# v01.net
KiCad netlist of a schematic drawn in EAGLE
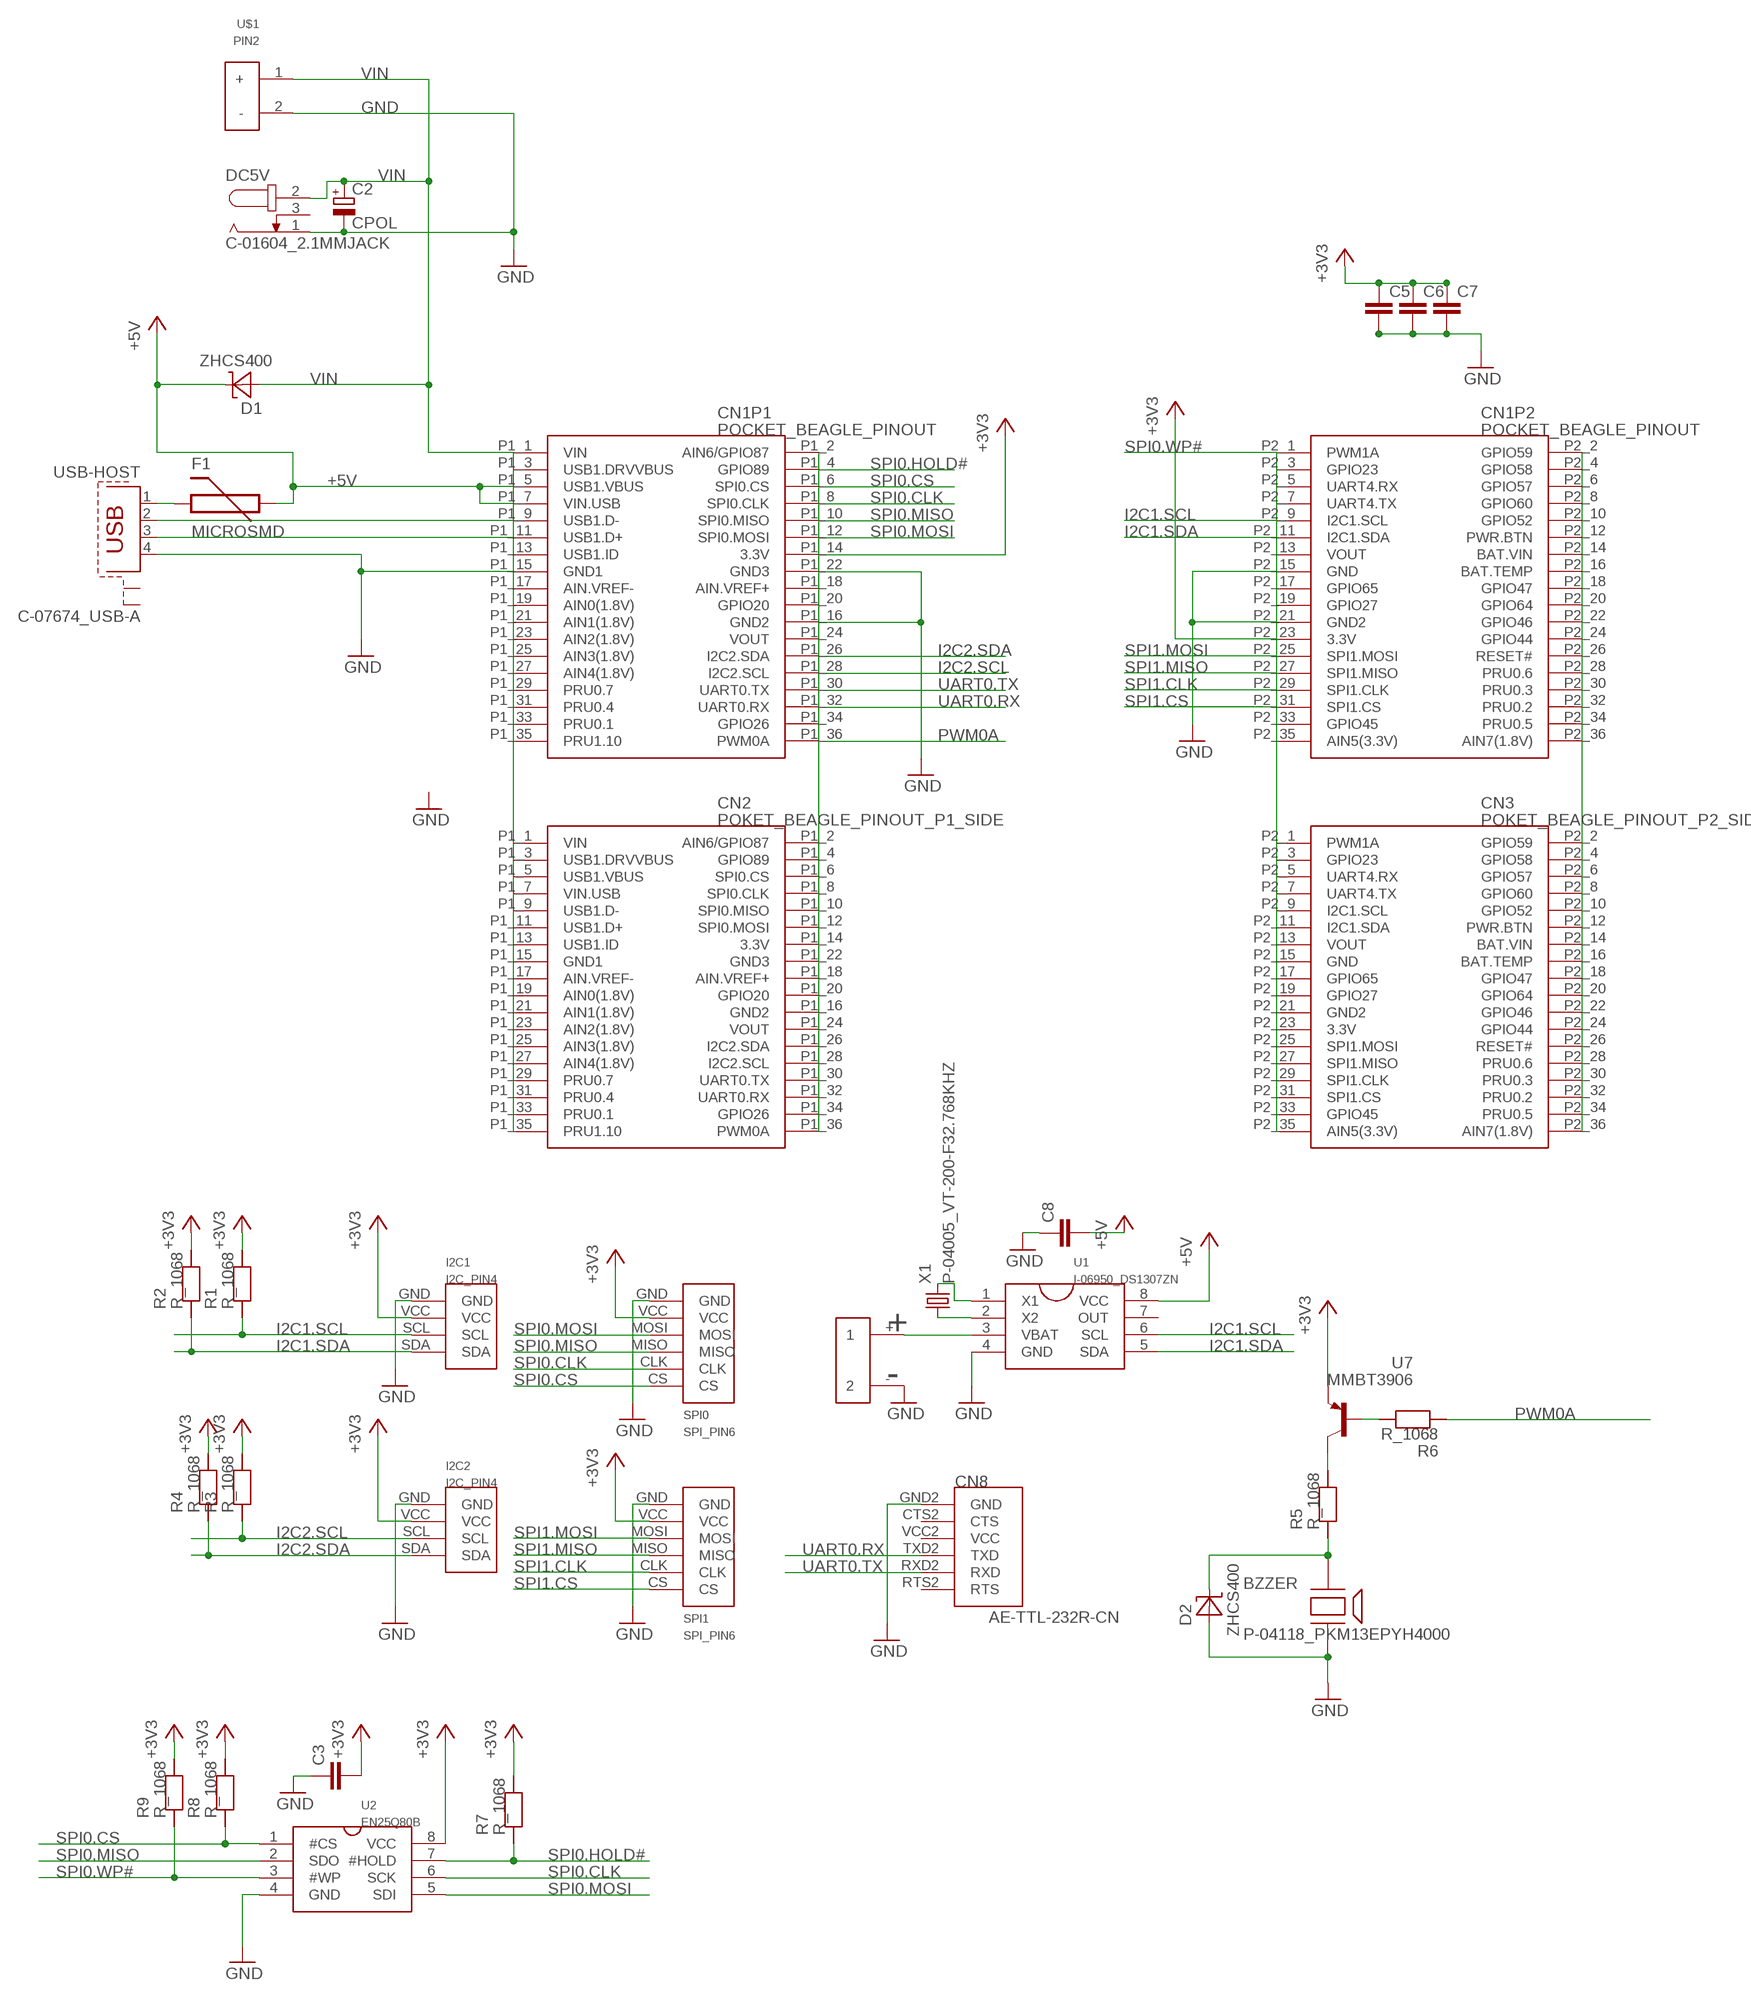
[diagram p0: schematic, sheet 1]

(export (version "E")
  (design (tool "Eeschema 10.0.6"))
  (components
    (comp (ref "BZZER")
      (value "P-04118_PKM13EPYH4000")
      (footprint "eagle-import:PKM13EPYH4000")
      (libsource (lib "eagle-import") (part "P-04118_PKM13EPYH4000"))
    )
    (comp (ref "C2")
      (value "CPOL")
      (footprint "eagle-import:153CLV-0605")
      (libsource (lib "eagle-import") (part "CPOL"))
    )
    (comp (ref "C3")
      (value "C_1068")
      (footprint "eagle-import:C0603")
      (libsource (lib "eagle-import") (part "C_1068"))
    )
    (comp (ref "C5")
      (value "C_2012")
      (footprint "eagle-import:C0805K")
      (libsource (lib "eagle-import") (part "C_2012"))
    )
    (comp (ref "C6")
      (value "C_1068")
      (footprint "eagle-import:C0603")
      (libsource (lib "eagle-import") (part "C_1068"))
    )
    (comp (ref "C7")
      (value "C_1068")
      (footprint "eagle-import:C0603")
      (libsource (lib "eagle-import") (part "C_1068"))
    )
    (comp (ref "C8")
      (value "C_1068")
      (footprint "eagle-import:C0603")
      (libsource (lib "eagle-import") (part "C_1068"))
    )
    (comp (ref "CN1")
      (value "POCKET_BEAGLE_PINOUT")
      (footprint "eagle-import:POCKET_BEAGLE_PINOUT")
      (libsource (lib "eagle-import") (part "POCKET_BEAGLE_PINOUT"))
    )
    (comp (ref "CN2")
      (value "POKET_BEAGLE_PINOUT_P1_SIDE")
      (footprint "eagle-import:POKET_BEAGLE_PINOUT_P1_SIDE")
      (libsource (lib "eagle-import") (part "POKET_BEAGLE_PINOUT_P1_SIDE"))
    )
    (comp (ref "CN3")
      (value "POKET_BEAGLE_PINOUT_P2_SIDE")
      (footprint "eagle-import:POKET_BEAGLE_PINOUT_P2_SIDE")
      (libsource (lib "eagle-import") (part "POKET_BEAGLE_PINOUT_P2_SIDE"))
    )
    (comp (ref "CN8")
      (value "AE-TTL-232R-CN")
      (footprint "eagle-import:AE-TTL-232R-CN")
      (libsource (lib "eagle-import") (part "AE-TTL-232R-CN"))
    )
    (comp (ref "CR2032")
      (value "P-00706_CH25-2032LF")
      (footprint "eagle-import:CH25-2032LF")
      (libsource (lib "eagle-import") (part "P-00706_CH25-2032LF"))
    )
    (comp (ref "D1")
      (value "ZHCS400")
      (footprint "eagle-import:SOD323-W")
      (libsource (lib "eagle-import") (part "ZHCS400"))
    )
    (comp (ref "D2")
      (value "ZHCS400")
      (footprint "eagle-import:SOD323-W")
      (libsource (lib "eagle-import") (part "ZHCS400"))
    )
    (comp (ref "DC5V")
      (value "C-01604_2.1MMJACK")
      (footprint "eagle-import:2.1MMJACK")
      (libsource (lib "eagle-import") (part "C-01604_2.1MMJACK"))
    )
    (comp (ref "F1")
      (value "MICROSMD")
      (footprint "eagle-import:MICROSMD")
      (libsource (lib "eagle-import") (part "MICROSMD"))
    )
    (comp (ref "I2C1")
      (value "I2C_PIN4")
      (footprint "eagle-import:I2C_PIN4")
      (libsource (lib "eagle-import") (part "I2C_PIN4"))
    )
    (comp (ref "I2C2")
      (value "I2C_PIN4")
      (footprint "eagle-import:I2C_PIN4")
      (libsource (lib "eagle-import") (part "I2C_PIN4"))
    )
    (comp (ref "R1")
      (value "R_1068")
      (footprint "eagle-import:R0603")
      (libsource (lib "eagle-import") (part "R_1068"))
    )
    (comp (ref "R2")
      (value "R_1068")
      (footprint "eagle-import:R0603")
      (libsource (lib "eagle-import") (part "R_1068"))
    )
    (comp (ref "R3")
      (value "R_1068")
      (footprint "eagle-import:R0603")
      (libsource (lib "eagle-import") (part "R_1068"))
    )
    (comp (ref "R4")
      (value "R_1068")
      (footprint "eagle-import:R0603")
      (libsource (lib "eagle-import") (part "R_1068"))
    )
    (comp (ref "R5")
      (value "R_1068")
      (footprint "eagle-import:R0603")
      (libsource (lib "eagle-import") (part "R_1068"))
    )
    (comp (ref "R6")
      (value "R_1068")
      (footprint "eagle-import:R0603")
      (libsource (lib "eagle-import") (part "R_1068"))
    )
    (comp (ref "R7")
      (value "R_1068")
      (footprint "eagle-import:R0603")
      (libsource (lib "eagle-import") (part "R_1068"))
    )
    (comp (ref "R8")
      (value "R_1068")
      (footprint "eagle-import:R0603")
      (libsource (lib "eagle-import") (part "R_1068"))
    )
    (comp (ref "R9")
      (value "R_1068")
      (footprint "eagle-import:R0603")
      (libsource (lib "eagle-import") (part "R_1068"))
    )
    (comp (ref "SPI0")
      (value "SPI_PIN6")
      (footprint "eagle-import:SPI_PIN6")
      (libsource (lib "eagle-import") (part "SPI_PIN6"))
    )
    (comp (ref "SPI1")
      (value "SPI_PIN6")
      (footprint "eagle-import:SPI_PIN6")
      (libsource (lib "eagle-import") (part "SPI_PIN6"))
    )
    (comp (ref "U$1")
      (value "PIN2")
      (footprint "eagle-import:PIN2")
      (libsource (lib "eagle-import") (part "PIN2"))
    )
    (comp (ref "U1")
      (value "I-06950_DS1307ZN")
      (footprint "eagle-import:SO8")
      (libsource (lib "eagle-import") (part "I-06950_DS1307ZN"))
    )
    (comp (ref "U2")
      (value "EN25Q80B")
      (footprint "eagle-import:SO8")
      (libsource (lib "eagle-import") (part "EN25Q80B"))
    )
    (comp (ref "U7")
      (value "MMBT3906")
      (footprint "eagle-import:SOT23")
      (libsource (lib "eagle-import") (part "MMBT3906"))
    )
    (comp (ref "USB-HOST")
      (value "C-07674_USB-A")
      (footprint "eagle-import:PN87520-S")
      (libsource (lib "eagle-import") (part "C-07674_USB-A"))
    )
    (comp (ref "X1")
      (value "P-04005_VT-200-F32.768KHZ")
      (footprint "eagle-import:VT-200F")
      (libsource (lib "eagle-import") (part "P-04005_VT-200-F32.768KHZ"))
    )
  )
  (nets
    (net (code "1") (name "+3V3") (class "Default")
      (node (ref "C3") (pin "2") (pinfunction "2_2") (pintype "passive"))
      (node (ref "C5") (pin "1") (pinfunction "1_1") (pintype "passive"))
      (node (ref "C6") (pin "1") (pinfunction "1_1") (pintype "passive"))
      (node (ref "C7") (pin "1") (pinfunction "1_1") (pintype "passive"))
      (node (ref "CN1") (pin "P1_14") (pinfunction "3.3V_P1_14") (pintype "bidirectional"))
      (node (ref "CN1") (pin "P2_23") (pinfunction "3.3V_P2_23") (pintype "bidirectional"))
      (node (ref "CN2") (pin "P1_14") (pinfunction "3.3V_P1_14") (pintype "bidirectional"))
      (node (ref "CN3") (pin "P2_23") (pinfunction "3.3V_P2_23") (pintype "bidirectional"))
      (node (ref "I2C1") (pin "VCC") (pinfunction "VCC_VCC") (pintype "bidirectional"))
      (node (ref "I2C2") (pin "VCC") (pinfunction "VCC_VCC") (pintype "bidirectional"))
      (node (ref "R1") (pin "2") (pinfunction "2_2") (pintype "bidirectional"))
      (node (ref "R2") (pin "2") (pinfunction "2_2") (pintype "bidirectional"))
      (node (ref "R3") (pin "2") (pinfunction "2_2") (pintype "bidirectional"))
      (node (ref "R4") (pin "2") (pinfunction "2_2") (pintype "bidirectional"))
      (node (ref "R7") (pin "2") (pinfunction "2_2") (pintype "bidirectional"))
      (node (ref "R8") (pin "2") (pinfunction "2_2") (pintype "bidirectional"))
      (node (ref "R9") (pin "2") (pinfunction "2_2") (pintype "bidirectional"))
      (node (ref "SPI0") (pin "VCC") (pinfunction "VCC_VCC") (pintype "bidirectional"))
      (node (ref "SPI1") (pin "VCC") (pinfunction "VCC_VCC") (pintype "bidirectional"))
      (node (ref "U2") (pin "8") (pinfunction "VCC_8") (pintype "bidirectional"))
      (node (ref "U7") (pin "2") (pinfunction "E_2") (pintype "passive"))
    )
    (net (code "2") (name "+5V") (class "Default")
      (node (ref "C8") (pin "2") (pinfunction "2_2") (pintype "passive"))
      (node (ref "CN1") (pin "P1_5") (pinfunction "USB1.VBUS_P1_5") (pintype "bidirectional"))
      (node (ref "CN1") (pin "P1_7") (pinfunction "VIN.USB_P1_7") (pintype "bidirectional"))
      (node (ref "CN2") (pin "P1_5") (pinfunction "USB1.VBUS_P1_5") (pintype "bidirectional"))
      (node (ref "CN2") (pin "P1_7") (pinfunction "VIN.USB_P1_7") (pintype "bidirectional"))
      (node (ref "D1") (pin "C") (pinfunction "C_C") (pintype "passive"))
      (node (ref "F1") (pin "P$2") (pinfunction "P$2_P$2") (pintype "bidirectional"))
      (node (ref "U1") (pin "8") (pinfunction "VCC_8") (pintype "bidirectional"))
    )
    (net (code "3") (name "/I2C1.SCL") (class "Default")
      (node (ref "CN1") (pin "P2_9") (pinfunction "I2C1.SCL_P2_9") (pintype "bidirectional"))
      (node (ref "CN3") (pin "P2_9") (pinfunction "I2C1.SCL_P2_9") (pintype "bidirectional"))
      (node (ref "I2C1") (pin "SCL") (pinfunction "SCL_SCL") (pintype "bidirectional"))
      (node (ref "R1") (pin "1") (pinfunction "1_1") (pintype "bidirectional"))
      (node (ref "U1") (pin "6") (pinfunction "SCL_6") (pintype "bidirectional"))
    )
    (net (code "4") (name "/I2C1.SDA") (class "Default")
      (node (ref "CN1") (pin "P2_11") (pinfunction "I2C1.SDA_P2_11") (pintype "bidirectional"))
      (node (ref "CN3") (pin "P2_11") (pinfunction "I2C1.SDA_P2_11") (pintype "bidirectional"))
      (node (ref "I2C1") (pin "SDA") (pinfunction "SDA_SDA") (pintype "bidirectional"))
      (node (ref "R2") (pin "1") (pinfunction "1_1") (pintype "bidirectional"))
      (node (ref "U1") (pin "5") (pinfunction "SDA_5") (pintype "bidirectional"))
    )
    (net (code "5") (name "/I2C2.SCL") (class "Default")
      (node (ref "CN1") (pin "P1_28") (pinfunction "I2C2.SCL_P1_28") (pintype "bidirectional"))
      (node (ref "CN2") (pin "P1_28") (pinfunction "I2C2.SCL_P1_28") (pintype "bidirectional"))
      (node (ref "I2C2") (pin "SCL") (pinfunction "SCL_SCL") (pintype "bidirectional"))
      (node (ref "R3") (pin "1") (pinfunction "1_1") (pintype "bidirectional"))
    )
    (net (code "6") (name "/I2C2.SDA") (class "Default")
      (node (ref "CN1") (pin "P1_26") (pinfunction "I2C2.SDA_P1_26") (pintype "bidirectional"))
      (node (ref "CN2") (pin "P1_26") (pinfunction "I2C2.SDA_P1_26") (pintype "bidirectional"))
      (node (ref "I2C2") (pin "SDA") (pinfunction "SDA_SDA") (pintype "bidirectional"))
      (node (ref "R4") (pin "1") (pinfunction "1_1") (pintype "bidirectional"))
    )
    (net (code "7") (name "/PWM0A") (class "Default")
      (node (ref "CN1") (pin "P1_36") (pinfunction "PWM0A_P1_36") (pintype "bidirectional"))
      (node (ref "CN2") (pin "P1_36") (pinfunction "PWM0A_P1_36") (pintype "bidirectional"))
      (node (ref "R6") (pin "1") (pinfunction "1_1") (pintype "bidirectional"))
    )
    (net (code "8") (name "/SPI0.CLK") (class "Default")
      (node (ref "CN1") (pin "P1_8") (pinfunction "SPI0.CLK_P1_8") (pintype "bidirectional"))
      (node (ref "CN2") (pin "P1_8") (pinfunction "SPI0.CLK_P1_8") (pintype "bidirectional"))
      (node (ref "SPI0") (pin "CLK") (pinfunction "CLK_CLK") (pintype "bidirectional"))
      (node (ref "U2") (pin "6") (pinfunction "SCK_6") (pintype "bidirectional"))
    )
    (net (code "9") (name "/SPI0.CS") (class "Default")
      (node (ref "CN1") (pin "P1_6") (pinfunction "SPI0.CS_P1_6") (pintype "bidirectional"))
      (node (ref "CN2") (pin "P1_6") (pinfunction "SPI0.CS_P1_6") (pintype "bidirectional"))
      (node (ref "R8") (pin "1") (pinfunction "1_1") (pintype "bidirectional"))
      (node (ref "SPI0") (pin "CS") (pinfunction "CS_CS") (pintype "bidirectional"))
      (node (ref "U2") (pin "1") (pinfunction "#CS_1") (pintype "bidirectional"))
    )
    (net (code "10") (name "/SPI0.HOLD#") (class "Default")
      (node (ref "CN1") (pin "P1_4") (pinfunction "GPIO89_P1_4") (pintype "bidirectional"))
      (node (ref "CN2") (pin "P1_4") (pinfunction "GPIO89_P1_4") (pintype "bidirectional"))
      (node (ref "R7") (pin "1") (pinfunction "1_1") (pintype "bidirectional"))
      (node (ref "U2") (pin "7") (pinfunction "#HOLD_7") (pintype "bidirectional"))
    )
    (net (code "11") (name "/SPI0.MISO") (class "Default")
      (node (ref "CN1") (pin "P1_10") (pinfunction "SPI0.MISO_P1_10") (pintype "bidirectional"))
      (node (ref "CN2") (pin "P1_10") (pinfunction "SPI0.MISO_P1_10") (pintype "bidirectional"))
      (node (ref "SPI0") (pin "MISO") (pinfunction "MISO_MISO") (pintype "bidirectional"))
      (node (ref "U2") (pin "2") (pinfunction "SDO_2") (pintype "bidirectional"))
    )
    (net (code "12") (name "/SPI0.MOSI") (class "Default")
      (node (ref "CN1") (pin "P1_12") (pinfunction "SPI0.MOSI_P1_12") (pintype "bidirectional"))
      (node (ref "CN2") (pin "P1_12") (pinfunction "SPI0.MOSI_P1_12") (pintype "bidirectional"))
      (node (ref "SPI0") (pin "MOSI") (pinfunction "MOSI_MOSI") (pintype "bidirectional"))
      (node (ref "U2") (pin "5") (pinfunction "SDI_5") (pintype "bidirectional"))
    )
    (net (code "13") (name "/SPI0.WP#") (class "Default")
      (node (ref "CN1") (pin "P2_1") (pinfunction "PWM1A_P2_1") (pintype "bidirectional"))
      (node (ref "CN3") (pin "P2_1") (pinfunction "PWM1A_P2_1") (pintype "bidirectional"))
      (node (ref "R9") (pin "1") (pinfunction "1_1") (pintype "bidirectional"))
      (node (ref "U2") (pin "3") (pinfunction "#WP_3") (pintype "bidirectional"))
    )
    (net (code "14") (name "/SPI1.CLK") (class "Default")
      (node (ref "CN1") (pin "P2_29") (pinfunction "SPI1.CLK_P2_29") (pintype "bidirectional"))
      (node (ref "CN3") (pin "P2_29") (pinfunction "SPI1.CLK_P2_29") (pintype "bidirectional"))
      (node (ref "SPI1") (pin "CLK") (pinfunction "CLK_CLK") (pintype "bidirectional"))
    )
    (net (code "15") (name "/SPI1.CS") (class "Default")
      (node (ref "CN1") (pin "P2_31") (pinfunction "SPI1.CS_P2_31") (pintype "bidirectional"))
      (node (ref "CN3") (pin "P2_31") (pinfunction "SPI1.CS_P2_31") (pintype "bidirectional"))
      (node (ref "SPI1") (pin "CS") (pinfunction "CS_CS") (pintype "bidirectional"))
    )
    (net (code "16") (name "/SPI1.MISO") (class "Default")
      (node (ref "CN1") (pin "P2_27") (pinfunction "SPI1.MISO_P2_27") (pintype "bidirectional"))
      (node (ref "CN3") (pin "P2_27") (pinfunction "SPI1.MISO_P2_27") (pintype "bidirectional"))
      (node (ref "SPI1") (pin "MISO") (pinfunction "MISO_MISO") (pintype "bidirectional"))
    )
    (net (code "17") (name "/SPI1.MOSI") (class "Default")
      (node (ref "CN1") (pin "P2_25") (pinfunction "SPI1.MOSI_P2_25") (pintype "bidirectional"))
      (node (ref "CN3") (pin "P2_25") (pinfunction "SPI1.MOSI_P2_25") (pintype "bidirectional"))
      (node (ref "SPI1") (pin "MOSI") (pinfunction "MOSI_MOSI") (pintype "bidirectional"))
    )
    (net (code "18") (name "/UART0.RX") (class "Default")
      (node (ref "CN1") (pin "P1_32") (pinfunction "UART0.RX_P1_32") (pintype "bidirectional"))
      (node (ref "CN2") (pin "P1_32") (pinfunction "UART0.RX_P1_32") (pintype "bidirectional"))
      (node (ref "CN8") (pin "TXD2") (pinfunction "TXD_TXD2") (pintype "bidirectional"))
    )
    (net (code "19") (name "/UART0.TX") (class "Default")
      (node (ref "CN1") (pin "P1_30") (pinfunction "UART0.TX_P1_30") (pintype "bidirectional"))
      (node (ref "CN2") (pin "P1_30") (pinfunction "UART0.TX_P1_30") (pintype "bidirectional"))
      (node (ref "CN8") (pin "RXD2") (pinfunction "RXD_RXD2") (pintype "bidirectional"))
    )
    (net (code "20") (name "/VIN") (class "Default")
      (node (ref "C2") (pin "+") (pinfunction "+_+") (pintype "passive"))
      (node (ref "CN1") (pin "P1_1") (pinfunction "VIN_P1_1") (pintype "bidirectional"))
      (node (ref "CN2") (pin "P1_1") (pinfunction "VIN_P1_1") (pintype "bidirectional"))
      (node (ref "D1") (pin "A") (pinfunction "A_A") (pintype "passive"))
      (node (ref "DC5V") (pin "2") (pinfunction "VCC_2") (pintype "passive"))
      (node (ref "U$1") (pin "1") (pinfunction "+_1") (pintype "bidirectional"))
    )
    (net (code "21") (name "GND") (class "Default")
      (node (ref "BZZER") (pin "2") (pinfunction "2_2") (pintype "bidirectional"))
      (node (ref "C2") (pin "-") (pinfunction "-_-") (pintype "passive"))
      (node (ref "C3") (pin "1") (pinfunction "1_1") (pintype "passive"))
      (node (ref "C5") (pin "2") (pinfunction "2_2") (pintype "passive"))
      (node (ref "C6") (pin "2") (pinfunction "2_2") (pintype "passive"))
      (node (ref "C7") (pin "2") (pinfunction "2_2") (pintype "passive"))
      (node (ref "C8") (pin "1") (pinfunction "1_1") (pintype "passive"))
      (node (ref "CN1") (pin "P1_15") (pinfunction "GND1_P1_15") (pintype "bidirectional"))
      (node (ref "CN1") (pin "P1_16") (pinfunction "GND2_P1_16") (pintype "bidirectional"))
      (node (ref "CN1") (pin "P1_22") (pinfunction "GND3_P1_22") (pintype "bidirectional"))
      (node (ref "CN1") (pin "P2_15") (pinfunction "GND_P2_15") (pintype "bidirectional"))
      (node (ref "CN1") (pin "P2_21") (pinfunction "GND2_P2_21") (pintype "bidirectional"))
      (node (ref "CN2") (pin "P1_15") (pinfunction "GND1_P1_15") (pintype "bidirectional"))
      (node (ref "CN2") (pin "P1_16") (pinfunction "GND2_P1_16") (pintype "bidirectional"))
      (node (ref "CN2") (pin "P1_22") (pinfunction "GND3_P1_22") (pintype "bidirectional"))
      (node (ref "CN3") (pin "P2_15") (pinfunction "GND_P2_15") (pintype "bidirectional"))
      (node (ref "CN3") (pin "P2_21") (pinfunction "GND2_P2_21") (pintype "bidirectional"))
      (node (ref "CN8") (pin "GND2") (pinfunction "GND_GND2") (pintype "bidirectional"))
      (node (ref "CR2032") (pin "-") (pinfunction "2_-") (pintype "bidirectional"))
      (node (ref "D2") (pin "A") (pinfunction "A_A") (pintype "passive"))
      (node (ref "DC5V") (pin "1") (pinfunction "GND_1") (pintype "passive"))
      (node (ref "I2C1") (pin "GND") (pinfunction "GND_GND") (pintype "bidirectional"))
      (node (ref "I2C2") (pin "GND") (pinfunction "GND_GND") (pintype "bidirectional"))
      (node (ref "SPI0") (pin "GND") (pinfunction "GND_GND") (pintype "bidirectional"))
      (node (ref "SPI1") (pin "GND") (pinfunction "GND_GND") (pintype "bidirectional"))
      (node (ref "U$1") (pin "2") (pinfunction "-_2") (pintype "bidirectional"))
      (node (ref "U1") (pin "4") (pinfunction "GND_4") (pintype "bidirectional"))
      (node (ref "U2") (pin "4") (pinfunction "GND_4") (pintype "bidirectional"))
      (node (ref "USB-HOST") (pin "4") (pinfunction "4_4") (pintype "passive"))
    )
    (net (code "22") (name "Net-(BZZER-Pad1)") (class "Default")
      (node (ref "BZZER") (pin "1") (pinfunction "1_1") (pintype "bidirectional"))
      (node (ref "D2") (pin "C") (pinfunction "C_C") (pintype "passive"))
      (node (ref "R5") (pin "1") (pinfunction "1_1") (pintype "bidirectional"))
    )
    (net (code "23") (name "Net-(CN1A-AIN.VREF+)") (class "Default")
      (node (ref "CN1") (pin "P1_18") (pinfunction "AIN.VREF+_P1_18") (pintype "bidirectional"))
      (node (ref "CN2") (pin "P1_18") (pinfunction "AIN.VREF+_P1_18") (pintype "bidirectional"))
    )
    (net (code "24") (name "Net-(CN1A-AIN.VREF-)") (class "Default")
      (node (ref "CN1") (pin "P1_17") (pinfunction "AIN.VREF-_P1_17") (pintype "bidirectional"))
      (node (ref "CN2") (pin "P1_17") (pinfunction "AIN.VREF-_P1_17") (pintype "bidirectional"))
    )
    (net (code "25") (name "Net-(CN1A-AIN0(1.8V))") (class "Default")
      (node (ref "CN1") (pin "P1_19") (pinfunction "AIN0(1.8V)_P1_19") (pintype "bidirectional"))
      (node (ref "CN2") (pin "P1_19") (pinfunction "AIN0(1.8V)_P1_19") (pintype "bidirectional"))
    )
    (net (code "26") (name "Net-(CN1A-AIN1(1.8V))") (class "Default")
      (node (ref "CN1") (pin "P1_21") (pinfunction "AIN1(1.8V)_P1_21") (pintype "bidirectional"))
      (node (ref "CN2") (pin "P1_21") (pinfunction "AIN1(1.8V)_P1_21") (pintype "bidirectional"))
    )
    (net (code "27") (name "Net-(CN1A-AIN2(1.8V))") (class "Default")
      (node (ref "CN1") (pin "P1_23") (pinfunction "AIN2(1.8V)_P1_23") (pintype "bidirectional"))
      (node (ref "CN2") (pin "P1_23") (pinfunction "AIN2(1.8V)_P1_23") (pintype "bidirectional"))
    )
    (net (code "28") (name "Net-(CN1A-AIN3(1.8V))") (class "Default")
      (node (ref "CN1") (pin "P1_25") (pinfunction "AIN3(1.8V)_P1_25") (pintype "bidirectional"))
      (node (ref "CN2") (pin "P1_25") (pinfunction "AIN3(1.8V)_P1_25") (pintype "bidirectional"))
    )
    (net (code "29") (name "Net-(CN1A-AIN4(1.8V))") (class "Default")
      (node (ref "CN1") (pin "P1_27") (pinfunction "AIN4(1.8V)_P1_27") (pintype "bidirectional"))
      (node (ref "CN2") (pin "P1_27") (pinfunction "AIN4(1.8V)_P1_27") (pintype "bidirectional"))
    )
    (net (code "30") (name "Net-(CN1A-AIN6{slash}GPIO87)") (class "Default")
      (node (ref "CN1") (pin "P1_2") (pinfunction "AIN6/GPIO87_P1_2") (pintype "bidirectional"))
      (node (ref "CN2") (pin "P1_2") (pinfunction "AIN6/GPIO87_P1_2") (pintype "bidirectional"))
    )
    (net (code "31") (name "Net-(CN1A-GPIO20)") (class "Default")
      (node (ref "CN1") (pin "P1_20") (pinfunction "GPIO20_P1_20") (pintype "bidirectional"))
      (node (ref "CN2") (pin "P1_20") (pinfunction "GPIO20_P1_20") (pintype "bidirectional"))
    )
    (net (code "32") (name "Net-(CN1A-GPIO26)") (class "Default")
      (node (ref "CN1") (pin "P1_34") (pinfunction "GPIO26_P1_34") (pintype "bidirectional"))
      (node (ref "CN2") (pin "P1_34") (pinfunction "GPIO26_P1_34") (pintype "bidirectional"))
    )
    (net (code "33") (name "Net-(CN1A-PRU0.1)") (class "Default")
      (node (ref "CN1") (pin "P1_33") (pinfunction "PRU0.1_P1_33") (pintype "bidirectional"))
      (node (ref "CN2") (pin "P1_33") (pinfunction "PRU0.1_P1_33") (pintype "bidirectional"))
    )
    (net (code "34") (name "Net-(CN1A-PRU0.4)") (class "Default")
      (node (ref "CN1") (pin "P1_31") (pinfunction "PRU0.4_P1_31") (pintype "bidirectional"))
      (node (ref "CN2") (pin "P1_31") (pinfunction "PRU0.4_P1_31") (pintype "bidirectional"))
    )
    (net (code "35") (name "Net-(CN1A-PRU0.7)") (class "Default")
      (node (ref "CN1") (pin "P1_29") (pinfunction "PRU0.7_P1_29") (pintype "bidirectional"))
      (node (ref "CN2") (pin "P1_29") (pinfunction "PRU0.7_P1_29") (pintype "bidirectional"))
    )
    (net (code "36") (name "Net-(CN1A-PRU1.10)") (class "Default")
      (node (ref "CN1") (pin "P1_35") (pinfunction "PRU1.10_P1_35") (pintype "bidirectional"))
      (node (ref "CN2") (pin "P1_35") (pinfunction "PRU1.10_P1_35") (pintype "bidirectional"))
    )
    (net (code "37") (name "Net-(CN1A-USB1.D+)") (class "Default")
      (node (ref "CN1") (pin "P1_11") (pinfunction "USB1.D+_P1_11") (pintype "bidirectional"))
      (node (ref "CN2") (pin "P1_11") (pinfunction "USB1.D+_P1_11") (pintype "bidirectional"))
      (node (ref "USB-HOST") (pin "3") (pinfunction "3_3") (pintype "passive"))
    )
    (net (code "38") (name "Net-(CN1A-USB1.D-)") (class "Default")
      (node (ref "CN1") (pin "P1_9") (pinfunction "USB1.D-_P1_9") (pintype "bidirectional"))
      (node (ref "CN2") (pin "P1_9") (pinfunction "USB1.D-_P1_9") (pintype "bidirectional"))
      (node (ref "USB-HOST") (pin "2") (pinfunction "2_2") (pintype "passive"))
    )
    (net (code "39") (name "Net-(CN1A-USB1.DRVVBUS)") (class "Default")
      (node (ref "CN1") (pin "P1_3") (pinfunction "USB1.DRVVBUS_P1_3") (pintype "bidirectional"))
      (node (ref "CN2") (pin "P1_3") (pinfunction "USB1.DRVVBUS_P1_3") (pintype "bidirectional"))
    )
    (net (code "40") (name "Net-(CN1A-USB1.ID)") (class "Default")
      (node (ref "CN1") (pin "P1_13") (pinfunction "USB1.ID_P1_13") (pintype "bidirectional"))
      (node (ref "CN2") (pin "P1_13") (pinfunction "USB1.ID_P1_13") (pintype "bidirectional"))
    )
    (net (code "41") (name "Net-(CN1A-VOUT)") (class "Default")
      (node (ref "CN1") (pin "P1_24") (pinfunction "VOUT_P1_24") (pintype "bidirectional"))
      (node (ref "CN2") (pin "P1_24") (pinfunction "VOUT_P1_24") (pintype "bidirectional"))
    )
    (net (code "42") (name "Net-(CN1B-AIN5(3.3V))") (class "Default")
      (node (ref "CN1") (pin "P2_35") (pinfunction "AIN5(3.3V)_P2_35") (pintype "bidirectional"))
      (node (ref "CN3") (pin "P2_35") (pinfunction "AIN5(3.3V)_P2_35") (pintype "bidirectional"))
    )
    (net (code "43") (name "Net-(CN1B-AIN7(1.8V))") (class "Default")
      (node (ref "CN1") (pin "P2_36") (pinfunction "AIN7(1.8V)_P2_36") (pintype "bidirectional"))
      (node (ref "CN3") (pin "P2_36") (pinfunction "AIN7(1.8V)_P2_36") (pintype "bidirectional"))
    )
    (net (code "44") (name "Net-(CN1B-BAT.TEMP)") (class "Default")
      (node (ref "CN1") (pin "P2_16") (pinfunction "BAT.TEMP_P2_16") (pintype "bidirectional"))
      (node (ref "CN3") (pin "P2_16") (pinfunction "BAT.TEMP_P2_16") (pintype "bidirectional"))
    )
    (net (code "45") (name "Net-(CN1B-BAT.VIN)") (class "Default")
      (node (ref "CN1") (pin "P2_14") (pinfunction "BAT.VIN_P2_14") (pintype "bidirectional"))
      (node (ref "CN3") (pin "P2_14") (pinfunction "BAT.VIN_P2_14") (pintype "bidirectional"))
    )
    (net (code "46") (name "Net-(CN1B-GPIO23)") (class "Default")
      (node (ref "CN1") (pin "P2_3") (pinfunction "GPIO23_P2_3") (pintype "bidirectional"))
      (node (ref "CN3") (pin "P2_3") (pinfunction "GPIO23_P2_3") (pintype "bidirectional"))
    )
    (net (code "47") (name "Net-(CN1B-GPIO27)") (class "Default")
      (node (ref "CN1") (pin "P2_19") (pinfunction "GPIO27_P2_19") (pintype "bidirectional"))
      (node (ref "CN3") (pin "P2_19") (pinfunction "GPIO27_P2_19") (pintype "bidirectional"))
    )
    (net (code "48") (name "Net-(CN1B-GPIO44)") (class "Default")
      (node (ref "CN1") (pin "P2_24") (pinfunction "GPIO44_P2_24") (pintype "bidirectional"))
      (node (ref "CN3") (pin "P2_24") (pinfunction "GPIO44_P2_24") (pintype "bidirectional"))
    )
    (net (code "49") (name "Net-(CN1B-GPIO45)") (class "Default")
      (node (ref "CN1") (pin "P2_33") (pinfunction "GPIO45_P2_33") (pintype "bidirectional"))
      (node (ref "CN3") (pin "P2_33") (pinfunction "GPIO45_P2_33") (pintype "bidirectional"))
    )
    (net (code "50") (name "Net-(CN1B-GPIO46)") (class "Default")
      (node (ref "CN1") (pin "P2_22") (pinfunction "GPIO46_P2_22") (pintype "bidirectional"))
      (node (ref "CN3") (pin "P2_22") (pinfunction "GPIO46_P2_22") (pintype "bidirectional"))
    )
    (net (code "51") (name "Net-(CN1B-GPIO47)") (class "Default")
      (node (ref "CN1") (pin "P2_18") (pinfunction "GPIO47_P2_18") (pintype "bidirectional"))
      (node (ref "CN3") (pin "P2_18") (pinfunction "GPIO47_P2_18") (pintype "bidirectional"))
    )
    (net (code "52") (name "Net-(CN1B-GPIO52)") (class "Default")
      (node (ref "CN1") (pin "P2_10") (pinfunction "GPIO52_P2_10") (pintype "bidirectional"))
      (node (ref "CN3") (pin "P2_10") (pinfunction "GPIO52_P2_10") (pintype "bidirectional"))
    )
    (net (code "53") (name "Net-(CN1B-GPIO57)") (class "Default")
      (node (ref "CN1") (pin "P2_6") (pinfunction "GPIO57_P2_6") (pintype "bidirectional"))
      (node (ref "CN3") (pin "P2_6") (pinfunction "GPIO57_P2_6") (pintype "bidirectional"))
    )
    (net (code "54") (name "Net-(CN1B-GPIO58)") (class "Default")
      (node (ref "CN1") (pin "P2_4") (pinfunction "GPIO58_P2_4") (pintype "bidirectional"))
      (node (ref "CN3") (pin "P2_4") (pinfunction "GPIO58_P2_4") (pintype "bidirectional"))
    )
    (net (code "55") (name "Net-(CN1B-GPIO59)") (class "Default")
      (node (ref "CN1") (pin "P2_2") (pinfunction "GPIO59_P2_2") (pintype "bidirectional"))
      (node (ref "CN3") (pin "P2_2") (pinfunction "GPIO59_P2_2") (pintype "bidirectional"))
    )
    (net (code "56") (name "Net-(CN1B-GPIO60)") (class "Default")
      (node (ref "CN1") (pin "P2_8") (pinfunction "GPIO60_P2_8") (pintype "bidirectional"))
      (node (ref "CN3") (pin "P2_8") (pinfunction "GPIO60_P2_8") (pintype "bidirectional"))
    )
    (net (code "57") (name "Net-(CN1B-GPIO64)") (class "Default")
      (node (ref "CN1") (pin "P2_20") (pinfunction "GPIO64_P2_20") (pintype "bidirectional"))
      (node (ref "CN3") (pin "P2_20") (pinfunction "GPIO64_P2_20") (pintype "bidirectional"))
    )
    (net (code "58") (name "Net-(CN1B-GPIO65)") (class "Default")
      (node (ref "CN1") (pin "P2_17") (pinfunction "GPIO65_P2_17") (pintype "bidirectional"))
      (node (ref "CN3") (pin "P2_17") (pinfunction "GPIO65_P2_17") (pintype "bidirectional"))
    )
    (net (code "59") (name "Net-(CN1B-PRU0.2)") (class "Default")
      (node (ref "CN1") (pin "P2_32") (pinfunction "PRU0.2_P2_32") (pintype "bidirectional"))
      (node (ref "CN3") (pin "P2_32") (pinfunction "PRU0.2_P2_32") (pintype "bidirectional"))
    )
    (net (code "60") (name "Net-(CN1B-PRU0.3)") (class "Default")
      (node (ref "CN1") (pin "P2_30") (pinfunction "PRU0.3_P2_30") (pintype "bidirectional"))
      (node (ref "CN3") (pin "P2_30") (pinfunction "PRU0.3_P2_30") (pintype "bidirectional"))
    )
    (net (code "61") (name "Net-(CN1B-PRU0.5)") (class "Default")
      (node (ref "CN1") (pin "P2_34") (pinfunction "PRU0.5_P2_34") (pintype "bidirectional"))
      (node (ref "CN3") (pin "P2_34") (pinfunction "PRU0.5_P2_34") (pintype "bidirectional"))
    )
    (net (code "62") (name "Net-(CN1B-PRU0.6)") (class "Default")
      (node (ref "CN1") (pin "P2_28") (pinfunction "PRU0.6_P2_28") (pintype "bidirectional"))
      (node (ref "CN3") (pin "P2_28") (pinfunction "PRU0.6_P2_28") (pintype "bidirectional"))
    )
    (net (code "63") (name "Net-(CN1B-PWR.BTN)") (class "Default")
      (node (ref "CN1") (pin "P2_12") (pinfunction "PWR.BTN_P2_12") (pintype "bidirectional"))
      (node (ref "CN3") (pin "P2_12") (pinfunction "PWR.BTN_P2_12") (pintype "bidirectional"))
    )
    (net (code "64") (name "Net-(CN1B-RESET#)") (class "Default")
      (node (ref "CN1") (pin "P2_26") (pinfunction "RESET#_P2_26") (pintype "bidirectional"))
      (node (ref "CN3") (pin "P2_26") (pinfunction "RESET#_P2_26") (pintype "bidirectional"))
    )
    (net (code "65") (name "Net-(CN1B-UART4.RX)") (class "Default")
      (node (ref "CN1") (pin "P2_5") (pinfunction "UART4.RX_P2_5") (pintype "bidirectional"))
      (node (ref "CN3") (pin "P2_5") (pinfunction "UART4.RX_P2_5") (pintype "bidirectional"))
    )
    (net (code "66") (name "Net-(CN1B-UART4.TX)") (class "Default")
      (node (ref "CN1") (pin "P2_7") (pinfunction "UART4.TX_P2_7") (pintype "bidirectional"))
      (node (ref "CN3") (pin "P2_7") (pinfunction "UART4.TX_P2_7") (pintype "bidirectional"))
    )
    (net (code "67") (name "Net-(CN1B-VOUT)") (class "Default")
      (node (ref "CN1") (pin "P2_13") (pinfunction "VOUT_P2_13") (pintype "bidirectional"))
      (node (ref "CN3") (pin "P2_13") (pinfunction "VOUT_P2_13") (pintype "bidirectional"))
    )
    (net (code "68") (name "Net-(CR2032-1)") (class "Default")
      (node (ref "CR2032") (pin "+") (pinfunction "1_+") (pintype "bidirectional"))
      (node (ref "U1") (pin "3") (pinfunction "VBAT_3") (pintype "bidirectional"))
    )
    (net (code "69") (name "Net-(F1-PadP$1)") (class "Default")
      (node (ref "F1") (pin "P$1") (pinfunction "P$1_P$1") (pintype "bidirectional"))
      (node (ref "USB-HOST") (pin "1") (pinfunction "1_1") (pintype "passive"))
    )
    (net (code "70") (name "Net-(U1-X1)") (class "Default")
      (node (ref "U1") (pin "1") (pinfunction "X1_1") (pintype "bidirectional"))
      (node (ref "X1") (pin "2") (pinfunction "2_2") (pintype "passive"))
    )
    (net (code "71") (name "Net-(U1-X2)") (class "Default")
      (node (ref "U1") (pin "2") (pinfunction "X2_2") (pintype "bidirectional"))
      (node (ref "X1") (pin "1") (pinfunction "1_1") (pintype "passive"))
    )
    (net (code "72") (name "Net-(U7-B)") (class "Default")
      (node (ref "R6") (pin "2") (pinfunction "2_2") (pintype "bidirectional"))
      (node (ref "U7") (pin "1") (pinfunction "B_1") (pintype "passive"))
    )
    (net (code "73") (name "Net-(U7-C)") (class "Default")
      (node (ref "R5") (pin "2") (pinfunction "2_2") (pintype "bidirectional"))
      (node (ref "U7") (pin "3") (pinfunction "C_3") (pintype "passive"))
    )
    (net (code "74") (name "unconnected-(CN8-CTS-PadCTS2)") (class "Default")
      (node (ref "CN8") (pin "CTS2") (pinfunction "CTS_CTS2") (pintype "bidirectional"))
    )
    (net (code "75") (name "unconnected-(CN8-RTS-PadRTS2)") (class "Default")
      (node (ref "CN8") (pin "RTS2") (pinfunction "RTS_RTS2") (pintype "bidirectional"))
    )
    (net (code "76") (name "unconnected-(CN8-VCC-PadVCC2)") (class "Default")
      (node (ref "CN8") (pin "VCC2") (pinfunction "VCC_VCC2") (pintype "bidirectional"))
    )
    (net (code "77") (name "unconnected-(DC5V-S-Pad3)") (class "Default")
      (node (ref "DC5V") (pin "3") (pinfunction "S_3") (pintype "passive"))
    )
    (net (code "78") (name "unconnected-(U1-OUT-Pad7)") (class "Default")
      (node (ref "U1") (pin "7") (pinfunction "OUT_7") (pintype "bidirectional"))
    )
    (net (code "79") (name "unconnected-(USB-HOST-PadS1)") (class "Default")
      (node (ref "USB-HOST") (pin "S1") (pinfunction "S1_S1") (pintype "passive"))
    )
    (net (code "80") (name "unconnected-(USB-HOST-PadS2)") (class "Default")
      (node (ref "USB-HOST") (pin "S2") (pinfunction "S2_S2") (pintype "passive"))
    )
  )
)
